# SCH_VIPER12A.net
KiCad netlist of a schematic drawn in Altium Designer
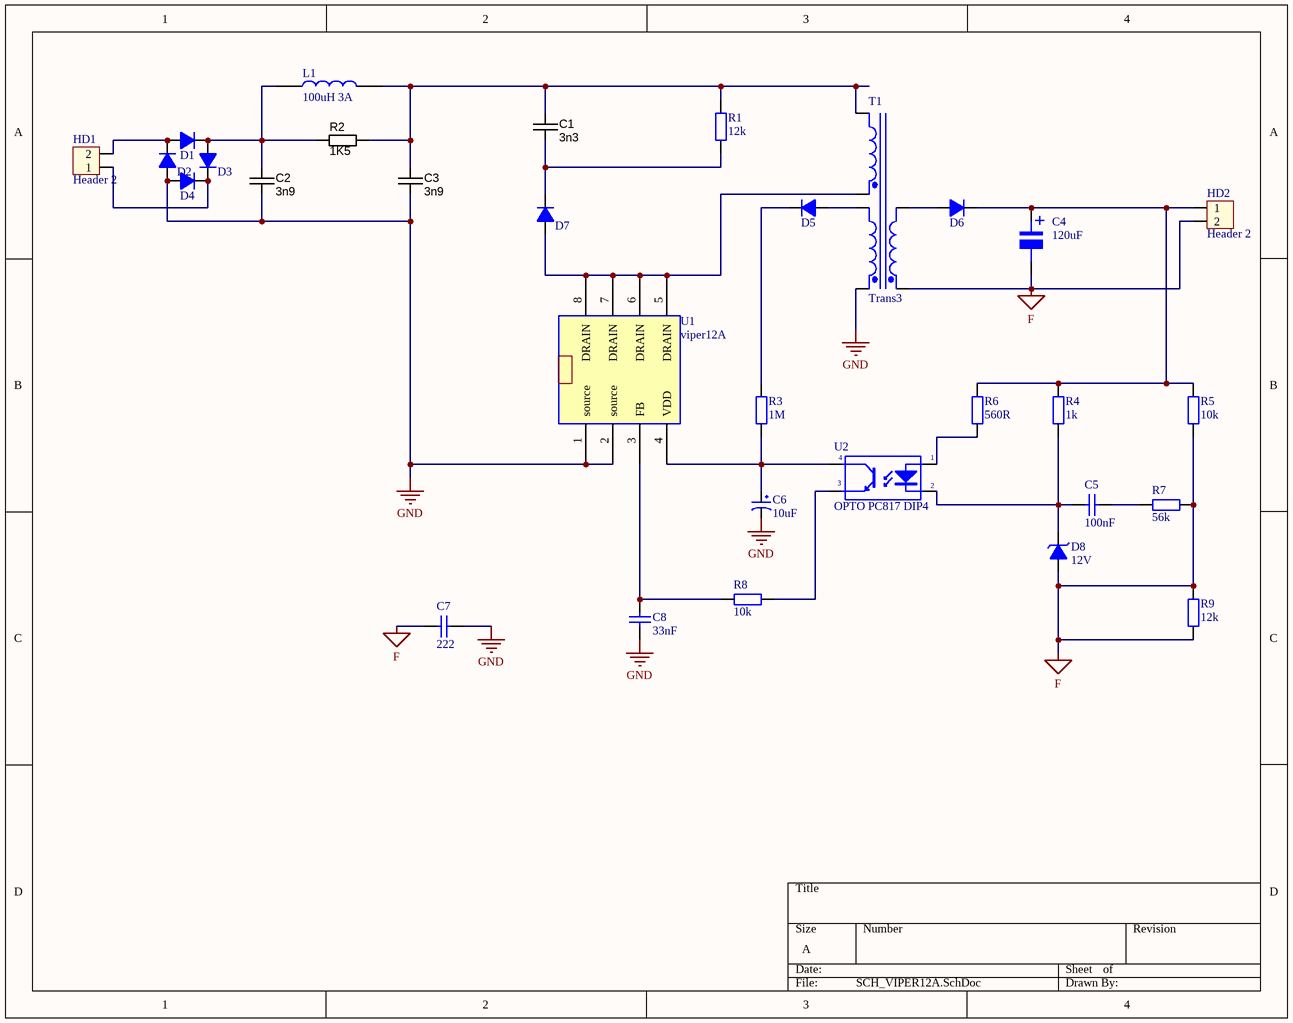
[diagram p0: SCH_VIPER12A.SchDoc]

(export (version "E")
  (design (tool "Eeschema 10.0.6"))
  (components
    (comp (ref "C1")
      (value "3n3")
      (footprint "CAPMF5.0-7.5mm_SL")
      (description "Capacitor THD Metallized PET Film 3.3nF 10% 400V")
      (fields (field (name "TOLERANCE") "±10%"))
      (libsource (lib "My library altium") (part "CAPMF_3n3_400V_MPET"))
    )
    (comp (ref "C2")
      (value "3n9")
      (footprint "CAPMF5.0-7.5mm_SL")
      (description "Capacitor THD Metallized PET Film 3.9nF 10% 400V")
      (fields (field (name "TOLERANCE") "±10%"))
      (libsource (lib "My library altium") (part "CAPMF_3n9_400V_MPET"))
    )
    (comp (ref "C3")
      (value "3n9")
      (footprint "CAPMF5.0-7.5mm_SL")
      (description "Capacitor THD Metallized PET Film 3.9nF 10% 400V")
      (fields (field (name "TOLERANCE") "±10%"))
      (libsource (lib "My library altium") (part "CAPMF_3n9_400V_MPET"))
    )
    (comp (ref "C4")
      (value "120uF")
      (footprint "tu nhom 6.3 (d)")
      (description "Dán")
      (libsource (lib "Altium_Lib_by_KhueNguyenCreator") (part "Tu Nhom 120uF 10V"))
    )
    (comp (ref "C5")
      (value "100nF")
      (footprint "tu tantalum dip5.08")
      (description "Cắm")
      (libsource (lib "Altium_Lib_by_KhueNguyenCreator") (part "Tu tantalum 100nF 50V 20% DIP5.08"))
    )
    (comp (ref "C6")
      (value "10uF")
      (footprint "tu hoa 4mm")
      (description "Cắm")
      (libsource (lib "Altium_Lib_by_KhueNguyenCreator") (part "Tu Hoa 10uF 25V 4x7"))
    )
    (comp (ref "C7")
      (value "222")
      (footprint "tu gom")
      (description "Cắm")
      (libsource (lib "Altium_Lib_by_KhueNguyenCreator") (part "Tu gom 222 50V"))
    )
    (comp (ref "C8")
      (value "33nF")
      (footprint "tu 0402")
      (description "Dán")
      (libsource (lib "Altium_Lib_by_KhueNguyenCreator") (part "Tu 0402 33nF 10V"))
    )
    (comp (ref "D1")
      (value "Diode  1N4007")
      (footprint "DO-214AC")
      (description "Diode 1A")
      (libsource (lib "My library altium") (part "Diode  1N4007"))
    )
    (comp (ref "D2")
      (value "Diode  1N4007")
      (footprint "DO-214AC")
      (description "Diode 1A")
      (libsource (lib "My library altium") (part "Diode  1N4007"))
    )
    (comp (ref "D3")
      (value "Diode  1N4007")
      (footprint "DO-214AC")
      (description "Diode 1A")
      (libsource (lib "My library altium") (part "Diode  1N4007"))
    )
    (comp (ref "D4")
      (value "Diode  1N4007")
      (footprint "DO-214AC")
      (description "Diode 1A")
      (libsource (lib "My library altium") (part "Diode  1N4007"))
    )
    (comp (ref "D5")
      (value "Diode  1N4007")
      (footprint "DO-214AC")
      (description "Diode 1A")
      (libsource (lib "My library altium") (part "Diode  1N4007"))
    )
    (comp (ref "D6")
      (value "Diode  1N4007")
      (footprint "DO-214AC")
      (description "Diode 1A")
      (libsource (lib "My library altium") (part "Diode  1N4007"))
    )
    (comp (ref "D7")
      (value "Diode  1N4007")
      (footprint "DO-214AC")
      (description "Diode 1A")
      (libsource (lib "My library altium") (part "Diode  1N4007"))
    )
    (comp (ref "D8")
      (value "12V")
      (footprint "DIODE ZENNER SMD SOD80")
      (description "Dán")
      (libsource (lib "Altium_Lib_by_KhueNguyenCreator") (part "Diode Zener 12V"))
    )
    (comp (ref "HD1")
      (value "Header 2")
      (footprint "HED2")
      (description "Header 2 (Green)")
      (libsource (lib "") (part "Header 2_1"))
    )
    (comp (ref "HD2")
      (value "Header 2")
      (footprint "HED2")
      (description "Header 2 (Green)")
      (libsource (lib "My library altium") (part "Header 2"))
    )
    (comp (ref "L1")
      (value "100uH 3A")
      (footprint "CUON CAM 100uH3A")
      (description "Dán")
      (libsource (lib "Altium_Lib_by_KhueNguyenCreator") (part "CUON CAM 100uH DIP"))
    )
    (comp (ref "R1")
      (value "12k")
      (footprint "tro vach 1/4w")
      (description "Cắm")
      (libsource (lib "Altium_Lib_by_KhueNguyenCreator") (part "Tro Vach 1/4W 5% 12k"))
    )
    (comp (ref "R2")
      (value "1K5")
      (footprint "RESTH_AXIAL-0.4")
      (description "Resistor THD Axial 1.5k Ohm 0.5W 5% Carbon Film")
      (fields (field (name "TOLERANCE") "±5%") (field (name "Comment") "Carbon Film"))
      (libsource (lib "My library altium") (part "RES_Axial_0.5W"))
    )
    (comp (ref "R3")
      (value "1M")
      (footprint "tro smd 0603")
      (description "Dán")
      (libsource (lib "Altium_Lib_by_KhueNguyenCreator") (part "Tro 0603 5% 1M"))
    )
    (comp (ref "R4")
      (value "1k")
      (footprint "tro smd 1206")
      (description "Dán")
      (libsource (lib "Altium_Lib_by_KhueNguyenCreator") (part "Tro 1206 1% 1k"))
    )
    (comp (ref "R5")
      (value "10k")
      (footprint "tro smd 1206")
      (description "Dán")
      (libsource (lib "Altium_Lib_by_KhueNguyenCreator") (part "Tro 1206 1% 10k"))
    )
    (comp (ref "R6")
      (value "560R")
      (footprint "tro smd 0805")
      (description "Dán")
      (libsource (lib "Altium_Lib_by_KhueNguyenCreator") (part "Tro 0805 5% 560R"))
    )
    (comp (ref "R7")
      (value "56k")
      (footprint "tro vach 1/4w")
      (description "Cắm")
      (libsource (lib "Altium_Lib_by_KhueNguyenCreator") (part "Tro Vach 1/4W 5% 56k"))
    )
    (comp (ref "R8")
      (value "10k")
      (footprint "tro smd 2512")
      (description "Dán")
      (libsource (lib "Altium_Lib_by_KhueNguyenCreator") (part "Tro 2512 5% 10k"))
    )
    (comp (ref "R9")
      (value "12k")
      (footprint "tro vach 1/4w")
      (description "Cắm")
      (libsource (lib "Altium_Lib_by_KhueNguyenCreator") (part "Tro Vach 1/4W 5% 12k"))
    )
    (comp (ref "T1")
      (value "Trans3")
      (footprint "TRF_6")
      (description "Three-winding Transformer (Non-Ideal)")
      (fields (field (name "PUBLISHER") "Altium Limited"))
      (libsource (lib "Miscellaneous Devices") (part "Trans3"))
    )
    (comp (ref "U1")
      (value "viper12A")
      (footprint "DIP.100/8/W.300/L.400")
      (libsource (lib "My library altium") (part "viper12A"))
    )
    (comp (ref "U2")
      (value "OPTO PC817 DIP4")
      (footprint "DIP4")
      (description "Single Opto")
      (libsource (lib "Altium_Lib_by_KhueNguyenCreator") (part "OPTO PC817 DIP4"))
    )
  )
  (nets
    (net (code "1") (name "F") (class "Default")
      (node (ref "C4") (pin "2") (pinfunction "2_2") (pintype "passive"))
      (node (ref "C7") (pin "2") (pinfunction "2_2") (pintype "passive"))
      (node (ref "D8") (pin "1") (pinfunction "A_1") (pintype "passive"))
      (node (ref "HD2") (pin "2") (pinfunction "2_2") (pintype "passive"))
      (node (ref "R5") (pin "1") (pinfunction "1_1") (pintype "passive"))
      (node (ref "R7") (pin "2") (pinfunction "2_2") (pintype "passive"))
      (node (ref "R9") (pin "1") (pinfunction "1_1") (pintype "passive"))
      (node (ref "R9") (pin "2") (pinfunction "2_2") (pintype "passive"))
      (node (ref "T1") (pin "1") (pinfunction "Pri+_1") (pintype "passive"))
    )
    (net (code "2") (name "GND") (class "Default")
      (node (ref "C2") (pin "2") (pintype "passive"))
      (node (ref "C3") (pin "2") (pintype "passive"))
      (node (ref "C6") (pin "2") (pinfunction "2_2") (pintype "passive"))
      (node (ref "C7") (pin "1") (pinfunction "1_1") (pintype "passive"))
      (node (ref "C8") (pin "2") (pinfunction "2_2") (pintype "passive"))
      (node (ref "D2") (pin "A") (pinfunction "A_A") (pintype "passive"))
      (node (ref "D4") (pin "A") (pinfunction "A_A") (pintype "passive"))
      (node (ref "T1") (pin "3") (pinfunction "Sec1+_3") (pintype "passive"))
      (node (ref "U1") (pin "1") (pinfunction "source_1") (pintype "passive"))
      (node (ref "U1") (pin "2") (pinfunction "source_2") (pintype "passive"))
    )
    (net (code "3") (name "Net-(C1-Pad2)") (class "Default")
      (node (ref "C1") (pin "2") (pintype "passive"))
      (node (ref "D7") (pin "K") (pinfunction "K_K") (pintype "passive"))
      (node (ref "R1") (pin "1") (pinfunction "1_1") (pintype "passive"))
    )
    (net (code "4") (name "Net-(C2-Pad1)") (class "Default")
      (node (ref "C2") (pin "1") (pintype "passive"))
      (node (ref "D1") (pin "K") (pinfunction "K_K") (pintype "passive"))
      (node (ref "D3") (pin "A") (pinfunction "A_A") (pintype "passive"))
      (node (ref "L1") (pin "1") (pinfunction "1_1") (pintype "passive"))
      (node (ref "R2") (pin "1") (pinfunction "1_1") (pintype "passive"))
    )
    (net (code "5") (name "Net-(C4-Pad1)") (class "Default")
      (node (ref "C4") (pin "1") (pinfunction "1_1") (pintype "passive"))
      (node (ref "D6") (pin "K") (pinfunction "K_K") (pintype "passive"))
      (node (ref "HD2") (pin "1") (pinfunction "1_1") (pintype "passive"))
      (node (ref "R4") (pin "2") (pinfunction "2_2") (pintype "passive"))
      (node (ref "R5") (pin "2") (pinfunction "2_2") (pintype "passive"))
      (node (ref "R6") (pin "1") (pinfunction "1_1") (pintype "passive"))
    )
    (net (code "6") (name "Net-(C5-Pad2)") (class "Default")
      (node (ref "C5") (pin "2") (pinfunction "2_2") (pintype "passive"))
      (node (ref "R7") (pin "1") (pinfunction "1_1") (pintype "passive"))
    )
    (net (code "7") (name "Net-(D1-PadA)") (class "Default")
      (node (ref "D1") (pin "A") (pinfunction "A_A") (pintype "passive"))
      (node (ref "D2") (pin "K") (pinfunction "K_K") (pintype "passive"))
      (node (ref "HD1") (pin "2") (pinfunction "2_2") (pintype "passive"))
    )
    (net (code "8") (name "Net-(D3-PadK)") (class "Default")
      (node (ref "D3") (pin "K") (pinfunction "K_K") (pintype "passive"))
      (node (ref "D4") (pin "K") (pinfunction "K_K") (pintype "passive"))
      (node (ref "HD1") (pin "1") (pinfunction "1_1") (pintype "passive"))
    )
    (net (code "9") (name "Net-(D5-PadK)") (class "Default")
      (node (ref "D5") (pin "K") (pinfunction "K_K") (pintype "passive"))
      (node (ref "R3") (pin "2") (pinfunction "2_2") (pintype "passive"))
    )
    (net (code "10") (name "Net-(D8-K)") (class "Default")
      (node (ref "C5") (pin "1") (pinfunction "1_1") (pintype "passive"))
      (node (ref "D8") (pin "2") (pinfunction "K_2") (pintype "passive"))
      (node (ref "R4") (pin "1") (pinfunction "1_1") (pintype "passive"))
      (node (ref "U2") (pin "2") (pinfunction "K_2") (pintype "passive"))
    )
    (net (code "11") (name "Net-(T1-Pri-)") (class "Default")
      (node (ref "D6") (pin "A") (pinfunction "A_A") (pintype "passive"))
      (node (ref "T1") (pin "2") (pinfunction "Pri-_2") (pintype "passive"))
    )
    (net (code "12") (name "Net-(T1-Sec1-)") (class "Default")
      (node (ref "D5") (pin "A") (pinfunction "A_A") (pintype "passive"))
      (node (ref "T1") (pin "4") (pinfunction "Sec1-_4") (pintype "passive"))
    )
    (net (code "13") (name "Net-(T1-Sec2+)") (class "Default")
      (node (ref "D7") (pin "A") (pinfunction "A_A") (pintype "passive"))
      (node (ref "T1") (pin "5") (pinfunction "Sec2+_5") (pintype "passive"))
      (node (ref "U1") (pin "5") (pinfunction "DRAIN_5") (pintype "passive"))
      (node (ref "U1") (pin "6") (pinfunction "DRAIN_6") (pintype "passive"))
      (node (ref "U1") (pin "7") (pinfunction "DRAIN_7") (pintype "passive"))
      (node (ref "U1") (pin "8") (pinfunction "DRAIN_8") (pintype "passive"))
    )
    (net (code "14") (name "Net-(T1-Sec2-)") (class "Default")
      (node (ref "C1") (pin "1") (pintype "passive"))
      (node (ref "C3") (pin "1") (pintype "passive"))
      (node (ref "L1") (pin "2") (pinfunction "2_2") (pintype "passive"))
      (node (ref "R1") (pin "2") (pinfunction "2_2") (pintype "passive"))
      (node (ref "R2") (pin "2") (pinfunction "2_2") (pintype "passive"))
      (node (ref "T1") (pin "6") (pinfunction "Sec2-_6") (pintype "passive"))
    )
    (net (code "15") (name "Net-(U1-FB)") (class "Default")
      (node (ref "C8") (pin "1") (pinfunction "1_1") (pintype "passive"))
      (node (ref "R8") (pin "1") (pinfunction "1_1") (pintype "passive"))
      (node (ref "U1") (pin "3") (pinfunction "FB_3") (pintype "passive"))
    )
    (net (code "16") (name "Net-(U1-VDD)") (class "Default")
      (node (ref "C6") (pin "1") (pinfunction "1_1") (pintype "passive"))
      (node (ref "R3") (pin "1") (pinfunction "1_1") (pintype "passive"))
      (node (ref "U1") (pin "4") (pinfunction "VDD_4") (pintype "passive"))
      (node (ref "U2") (pin "4") (pinfunction "C_4") (pintype "passive"))
    )
    (net (code "17") (name "Net-(U2-A)") (class "Default")
      (node (ref "R6") (pin "2") (pinfunction "2_2") (pintype "passive"))
      (node (ref "U2") (pin "1") (pinfunction "A_1") (pintype "passive"))
    )
    (net (code "18") (name "Net-(U2-E)") (class "Default")
      (node (ref "R8") (pin "2") (pinfunction "2_2") (pintype "passive"))
      (node (ref "U2") (pin "3") (pinfunction "E_3") (pintype "passive"))
    )
  )
)
